# FPGA_CONFIG.net
KiCad netlist of a schematic drawn in Altium Designer
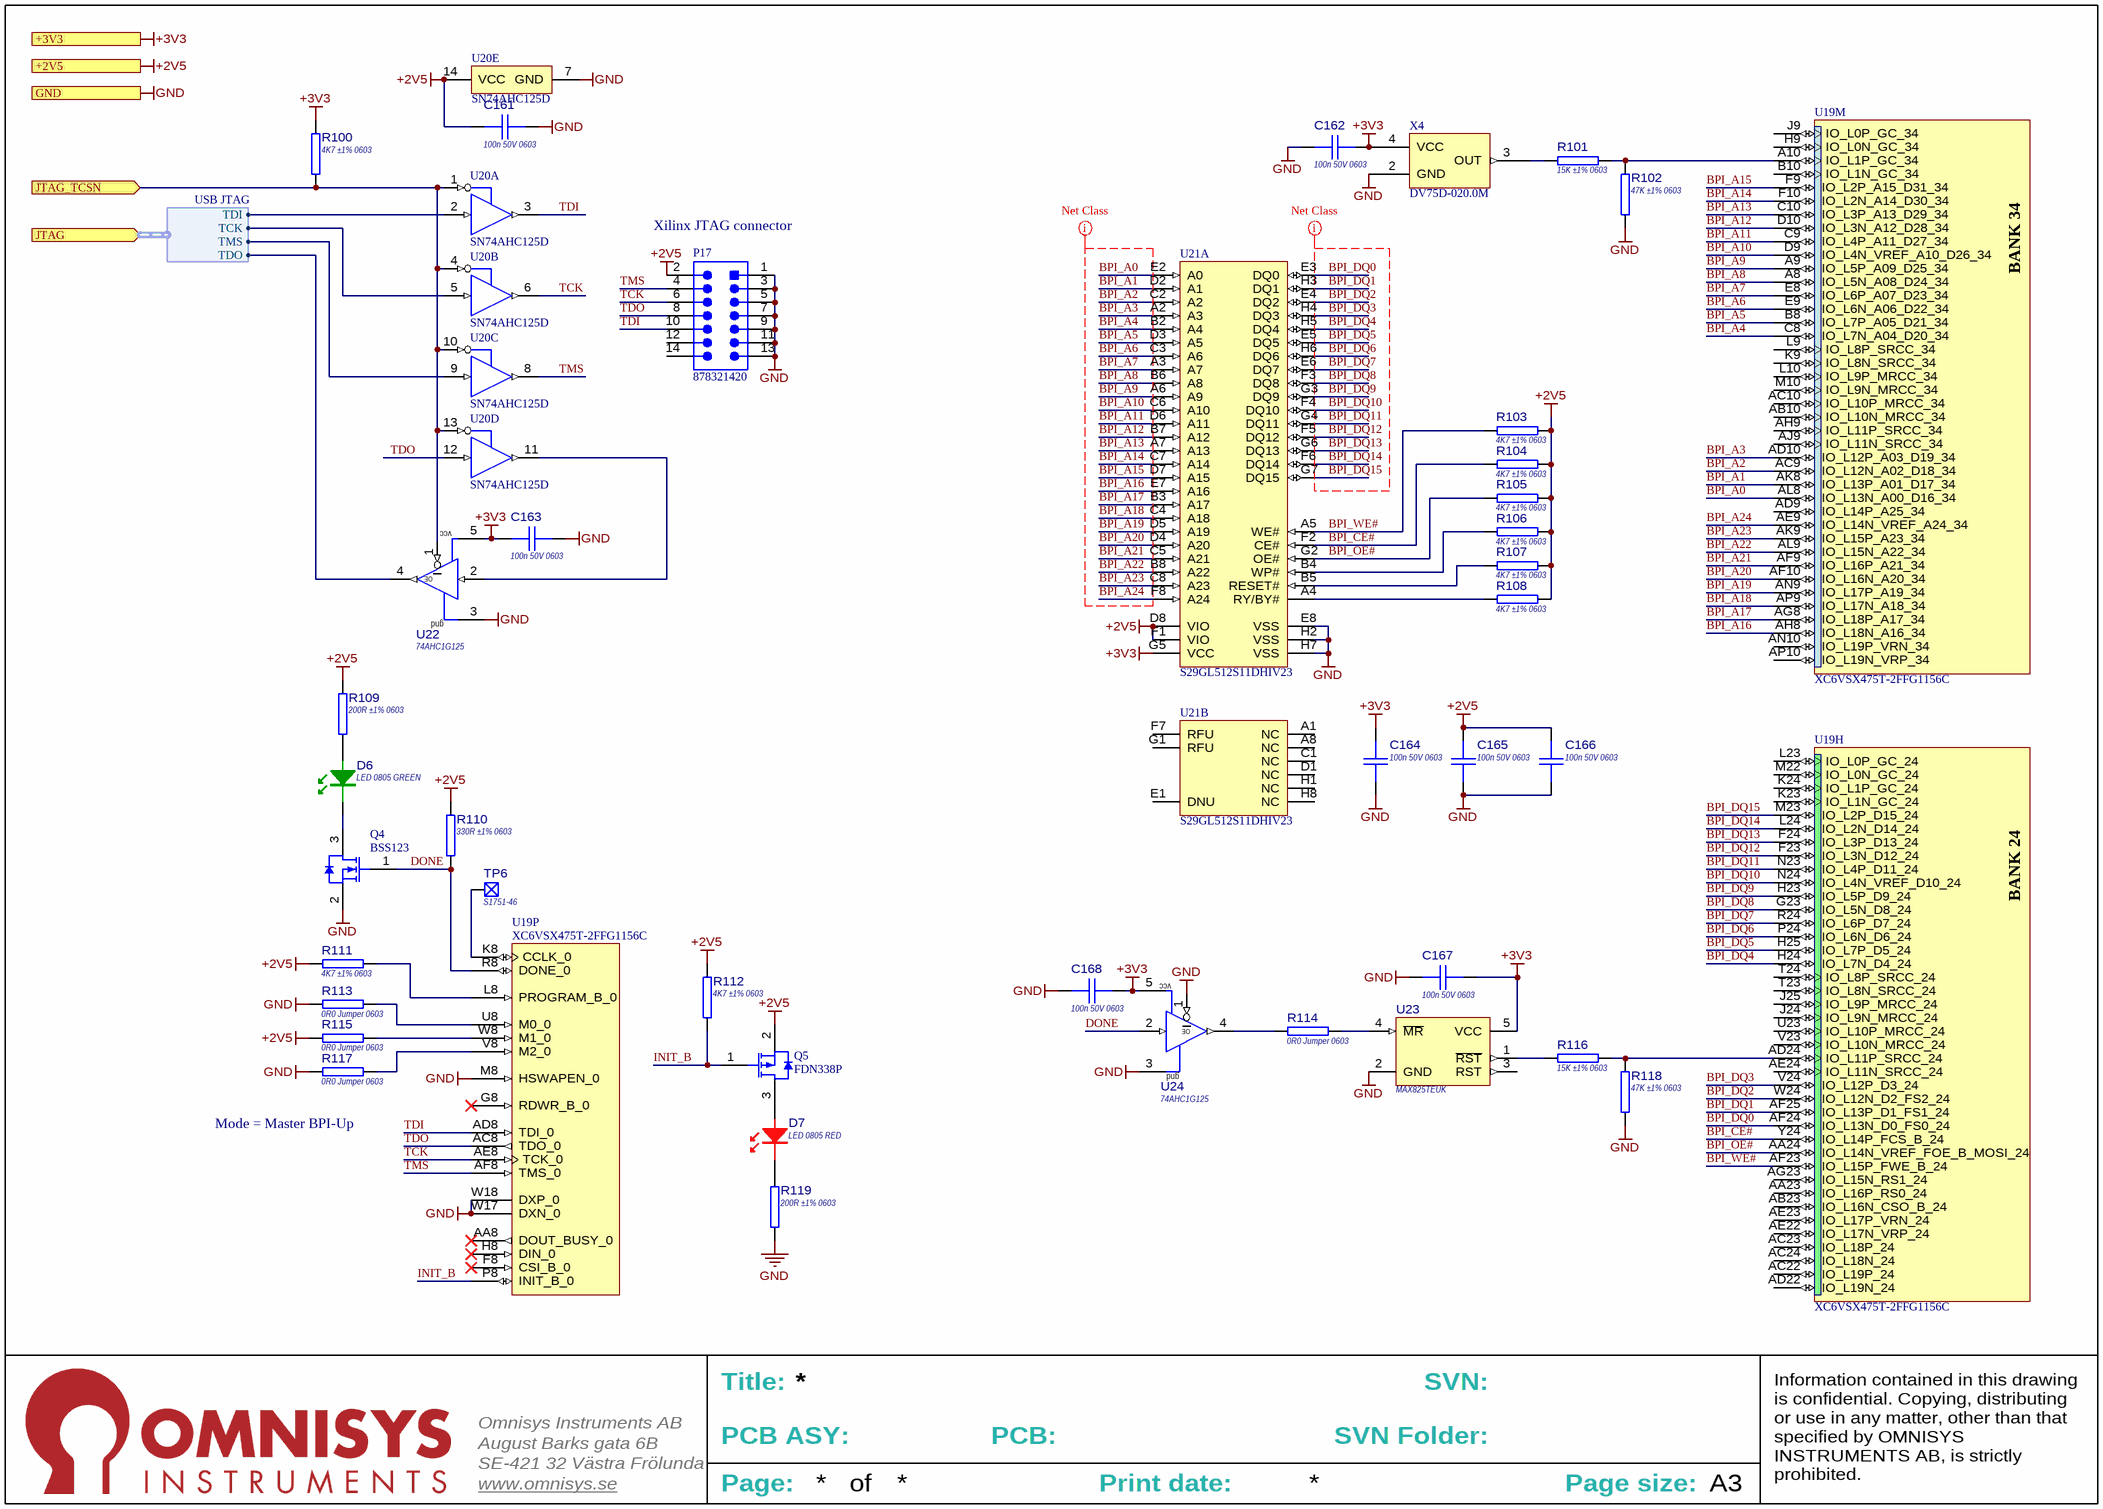
[diagram p0: FPGA_CONFIG.SchDoc]

(export (version "E")
  (design (tool "Eeschema 10.0.6"))
  (components
    (comp (ref "C161")
      (value "100n 50V 0603")
      (footprint "CAPC1608X90N")
      (description "100n 50V X7R ±10% 0603 (1608 metric)")
      (fields (field (name "PARTNUMBER") "GRM188R71H104KA93") (field (name "TOLERANCE") "±10%"))
      (libsource (lib "Omnisys Vault") (part "CAP-2PIN"))
    )
    (comp (ref "C162")
      (value "100n 50V 0603")
      (footprint "CAPC1608X90N")
      (description "100n 50V X7R ±10% 0603 (1608 metric)")
      (fields (field (name "PARTNUMBER") "GRM188R71H104KA93") (field (name "TOLERANCE") "±10%"))
      (libsource (lib "Omnisys Vault") (part "CAP-2PIN"))
    )
    (comp (ref "C163")
      (value "100n 50V 0603")
      (footprint "CAPC1608X90N")
      (description "100n 50V X7R ±10% 0603 (1608 metric)")
      (fields (field (name "PARTNUMBER") "GRM188R71H104KA93") (field (name "TOLERANCE") "±10%"))
      (libsource (lib "Omnisys Vault") (part "CAP-2PIN"))
    )
    (comp (ref "C164")
      (value "100n 50V 0603")
      (footprint "CAPC1608X90N")
      (description "100n 50V X7R ±10% 0603 (1608 metric)")
      (fields (field (name "PARTNUMBER") "GRM188R71H104KA93") (field (name "TOLERANCE") "±10%"))
      (libsource (lib "Omnisys Vault") (part "CAP-2PIN"))
    )
    (comp (ref "C165")
      (value "100n 50V 0603")
      (footprint "CAPC1608X90N")
      (description "100n 50V X7R ±10% 0603 (1608 metric)")
      (fields (field (name "PARTNUMBER") "GRM188R71H104KA93") (field (name "TOLERANCE") "±10%"))
      (libsource (lib "Omnisys Vault") (part "CAP-2PIN"))
    )
    (comp (ref "C166")
      (value "100n 50V 0603")
      (footprint "CAPC1608X90N")
      (description "100n 50V X7R ±10% 0603 (1608 metric)")
      (fields (field (name "PARTNUMBER") "GRM188R71H104KA93") (field (name "TOLERANCE") "±10%"))
      (libsource (lib "Omnisys Vault") (part "CAP-2PIN"))
    )
    (comp (ref "C167")
      (value "100n 50V 0603")
      (footprint "CAPC1608X90N")
      (description "100n 50V X7R ±10% 0603 (1608 metric)")
      (fields (field (name "PARTNUMBER") "GRM188R71H104KA93") (field (name "TOLERANCE") "±10%"))
      (libsource (lib "Omnisys Vault") (part "CAP-2PIN"))
    )
    (comp (ref "C168")
      (value "100n 50V 0603")
      (footprint "CAPC1608X90N")
      (description "100n 50V X7R ±10% 0603 (1608 metric)")
      (fields (field (name "PARTNUMBER") "GRM188R71H104KA93") (field (name "TOLERANCE") "±10%"))
      (libsource (lib "Omnisys Vault") (part "CAP-2PIN"))
    )
    (comp (ref "D6")
      (value "LED 0805 GREEN")
      (footprint "LED2012-GREEN")
      (libsource (lib "Omnisys Vault") (part "LED-2PIN-GREEN"))
    )
    (comp (ref "D7")
      (value "LED 0805 RED")
      (footprint "LED2012-RED")
      (libsource (lib "Omnisys Vault") (part "LED-2PIN-RED"))
    )
    (comp (ref "P17")
      (value "878321420")
      (footprint "MOLX-878321420_V")
      (description "Male Header, Pitch 2 mm, 2 x 7 Position, Height 7.6 mm, -55 to 105 degC, RoHS")
      (fields (field (name "MANUFACTURER") "Molex"))
      (libsource (lib "Altium Content Vault") (part "CN-2P-M-R14"))
    )
    (comp (ref "Q4")
      (value "BSS123")
      (footprint "FAIR-SOT23-3_V")
      (fields (field (name "MANUFACTURER") "Fairchild"))
      (libsource (lib "Altium Content Vault") (part "NEMOS-GSD-3"))
    )
    (comp (ref "Q5")
      (value "FDN338P")
      (footprint "FAIR-SSOT3L-3_V")
      (fields (field (name "MANUFACTURER") "Fairchild Semiconductor"))
      (libsource (lib "Altium Content Vault") (part "PEMOS-GSD-3"))
    )
    (comp (ref "R100")
      (value "4K7 ±1% 0603")
      (footprint "RESC1608N")
      (description "4K7 ±1% ±100 ppm/˚C 0.10W 75V 0603 (1608 metric)")
      (fields (field (name "POWER") "100mW") (field (name "TOLERANCE") "1%"))
      (libsource (lib "Omnisys Vault") (part "RES-2PIN"))
    )
    (comp (ref "R101")
      (value "15K ±1% 0603")
      (footprint "RESC1608N")
      (description "15K ±1% ±100 ppm/˚C 0.10W 75V 0603 (1608 metric)")
      (fields (field (name "POWER") "100mW") (field (name "TOLERANCE") "1%"))
      (libsource (lib "Omnisys Vault") (part "RES-2PIN"))
    )
    (comp (ref "R102")
      (value "47K ±1% 0603")
      (footprint "RESC1608N")
      (description "47K ±1% ±100 ppm/˚C 0.10W 75V 0603 (1608 metric)")
      (fields (field (name "POWER") "100mW") (field (name "TOLERANCE") "1%"))
      (libsource (lib "Omnisys Vault") (part "RES-2PIN"))
    )
    (comp (ref "R103")
      (value "4K7 ±1% 0603")
      (footprint "RESC1608N")
      (description "4K7 ±1% ±100 ppm/˚C 0.10W 75V 0603 (1608 metric)")
      (fields (field (name "POWER") "100mW") (field (name "TOLERANCE") "1%"))
      (libsource (lib "Omnisys Vault") (part "RES-2PIN"))
    )
    (comp (ref "R104")
      (value "4K7 ±1% 0603")
      (footprint "RESC1608N")
      (description "4K7 ±1% ±100 ppm/˚C 0.10W 75V 0603 (1608 metric)")
      (fields (field (name "POWER") "100mW") (field (name "TOLERANCE") "1%"))
      (libsource (lib "Omnisys Vault") (part "RES-2PIN"))
    )
    (comp (ref "R105")
      (value "4K7 ±1% 0603")
      (footprint "RESC1608N")
      (description "4K7 ±1% ±100 ppm/˚C 0.10W 75V 0603 (1608 metric)")
      (fields (field (name "POWER") "100mW") (field (name "TOLERANCE") "1%"))
      (libsource (lib "Omnisys Vault") (part "RES-2PIN"))
    )
    (comp (ref "R106")
      (value "4K7 ±1% 0603")
      (footprint "RESC1608N")
      (description "4K7 ±1% ±100 ppm/˚C 0.10W 75V 0603 (1608 metric)")
      (fields (field (name "POWER") "100mW") (field (name "TOLERANCE") "1%"))
      (libsource (lib "Omnisys Vault") (part "RES-2PIN"))
    )
    (comp (ref "R107")
      (value "4K7 ±1% 0603")
      (footprint "RESC1608N")
      (description "4K7 ±1% ±100 ppm/˚C 0.10W 75V 0603 (1608 metric)")
      (fields (field (name "POWER") "100mW") (field (name "TOLERANCE") "1%"))
      (libsource (lib "Omnisys Vault") (part "RES-2PIN"))
    )
    (comp (ref "R108")
      (value "4K7 ±1% 0603")
      (footprint "RESC1608N")
      (description "4K7 ±1% ±100 ppm/˚C 0.10W 75V 0603 (1608 metric)")
      (fields (field (name "POWER") "100mW") (field (name "TOLERANCE") "1%"))
      (libsource (lib "Omnisys Vault") (part "RES-2PIN"))
    )
    (comp (ref "R109")
      (value "200R ±1% 0603")
      (footprint "RESC1608N")
      (description "200R ±1% ±100 ppm/˚C 0.10W 75V 0603 (1608 metric)")
      (fields (field (name "POWER") "100mW") (field (name "TOLERANCE") "1%"))
      (libsource (lib "Omnisys Vault") (part "RES-2PIN"))
    )
    (comp (ref "R110")
      (value "330R ±1% 0603")
      (footprint "RESC1608N")
      (description "330R ±1% ±100 ppm/˚C 0.10W 75V 0603 (1608 metric)")
      (fields (field (name "POWER") "100mW") (field (name "TOLERANCE") "1%"))
      (libsource (lib "Omnisys Vault") (part "RES-2PIN"))
    )
    (comp (ref "R111")
      (value "4K7 ±1% 0603")
      (footprint "RESC1608N")
      (description "4K7 ±1% ±100 ppm/˚C 0.10W 75V 0603 (1608 metric)")
      (fields (field (name "POWER") "100mW") (field (name "TOLERANCE") "1%"))
      (libsource (lib "Omnisys Vault") (part "RES-2PIN"))
    )
    (comp (ref "R112")
      (value "4K7 ±1% 0603")
      (footprint "RESC1608N")
      (description "4K7 ±1% ±100 ppm/˚C 0.10W 75V 0603 (1608 metric)")
      (fields (field (name "POWER") "100mW") (field (name "TOLERANCE") "1%"))
      (libsource (lib "Omnisys Vault") (part "RES-2PIN"))
    )
    (comp (ref "R113")
      (value "0R0 Jumper 0603")
      (footprint "RESC1608N")
      (description "0R0 Jumper 75V 0603 (1608 metric) Max 2.0A")
      (fields (field (name "TOLERANCE") "0%") (field (name "POWER") "0W"))
      (libsource (lib "Omnisys Vault") (part "RES-2PIN"))
    )
    (comp (ref "R114")
      (value "0R0 Jumper 0603")
      (footprint "RESC1608N")
      (description "0R0 Jumper 75V 0603 (1608 metric) Max 2.0A")
      (fields (field (name "TOLERANCE") "0%") (field (name "POWER") "0W"))
      (libsource (lib "Omnisys Vault") (part "RES-2PIN"))
    )
    (comp (ref "R115")
      (value "0R0 Jumper 0603")
      (footprint "RESC1608N")
      (description "0R0 Jumper 75V 0603 (1608 metric) Max 2.0A")
      (fields (field (name "TOLERANCE") "0%") (field (name "POWER") "0W"))
      (libsource (lib "Omnisys Vault") (part "RES-2PIN"))
    )
    (comp (ref "R116")
      (value "15K ±1% 0603")
      (footprint "RESC1608N")
      (description "15K ±1% ±100 ppm/˚C 0.10W 75V 0603 (1608 metric)")
      (fields (field (name "POWER") "100mW") (field (name "TOLERANCE") "1%"))
      (libsource (lib "Omnisys Vault") (part "RES-2PIN"))
    )
    (comp (ref "R117")
      (value "0R0 Jumper 0603")
      (footprint "RESC1608N")
      (description "0R0 Jumper 75V 0603 (1608 metric) Max 2.0A")
      (fields (field (name "TOLERANCE") "0%") (field (name "POWER") "0W"))
      (libsource (lib "Omnisys Vault") (part "RES-2PIN"))
    )
    (comp (ref "R118")
      (value "47K ±1% 0603")
      (footprint "RESC1608N")
      (description "47K ±1% ±100 ppm/˚C 0.10W 75V 0603 (1608 metric)")
      (fields (field (name "POWER") "100mW") (field (name "TOLERANCE") "1%"))
      (libsource (lib "Omnisys Vault") (part "RES-2PIN"))
    )
    (comp (ref "R119")
      (value "200R ±1% 0603")
      (footprint "RESC1608N")
      (description "200R ±1% ±100 ppm/˚C 0.10W 75V 0603 (1608 metric)")
      (fields (field (name "POWER") "100mW") (field (name "TOLERANCE") "1%"))
      (libsource (lib "Omnisys Vault") (part "RES-2PIN"))
    )
    (comp (ref "TP6")
      (value "S1751-46")
      (footprint "S1751-46")
      (description "SMD Test point clip")
      (libsource (lib "Omnisys Vault") (part "1-PIN_TP"))
    )
    (comp (ref "U19")
      (value "XC6VSX475T-2FFG1156C")
      (footprint "FFG1156")
      (libsource (lib "Altium Content Vault") (part "FPGA-XVR6-XC6VXXXXXT-GA1156"))
    )
    (comp (ref "U20")
      (value "SN74AHC125D")
      (footprint "SOIC127P600X175-14N")
      (description "Buffer/Line Driver 4-CH Non-Inverting 3-ST CMOS 14-Pin SOIC Tube")
      (libsource (lib "Omnisys Vault") (part "SN74AHC125D"))
    )
    (comp (ref "U21")
      (value "S29GL512S11DHIV23")
      (footprint "BGA64C100P8X8_900X900X140")
      (description "IC FLASH MEM 512MBIT PAGE 64BGA")
      (libsource (lib "Omnisys Vault") (part "S29GL512S11DHIV23"))
    )
    (comp (ref "U22")
      (value "74AHC1G125")
      (footprint "SOT95P280X100-5N")
      (description "Single bus buffer gate with 3-state output")
      (libsource (lib "Omnisys Vault") (part "74AHC1G125"))
    )
    (comp (ref "U23")
      (value "MAX825TEUK")
      (footprint "SOT95P280X100-5N")
      (description "Microprocessor Supervisory Circuits With Watchdog Timer and Manual Reset SOT-23-5, reset th: 3.08V")
      (libsource (lib "Omnisys Vault") (part "MAX825_EUK"))
    )
    (comp (ref "U24")
      (value "74AHC1G125")
      (footprint "SOT95P280X100-5N")
      (description "Single bus buffer gate with 3-state output")
      (libsource (lib "Omnisys Vault") (part "74AHC1G125"))
    )
    (comp (ref "X4")
      (value "DV75D-020.0M")
      (footprint "SON127P420X200-4N")
      (description "OSC TCXO 20.000MHZ LVCMOS SMD")
      (libsource (lib "Omnisys Vault") (part "DV75D-020.0M"))
    )
  )
  (nets
    (net (code "3") (name "+2V5") (class "Default")
      (node (ref "C161") (pin "1") (pinfunction "1_1") (pintype "passive"))
      (node (ref "C165") (pin "1") (pinfunction "1_1") (pintype "passive"))
      (node (ref "C166") (pin "1") (pinfunction "1_1") (pintype "passive"))
      (node (ref "P17") (pin "2") (pinfunction "2_2") (pintype "passive"))
      (node (ref "Q5") (pin "2") (pinfunction "SOURCE_2") (pintype "passive"))
      (node (ref "R103") (pin "1") (pinfunction "1_1") (pintype "passive"))
      (node (ref "R104") (pin "1") (pinfunction "1_1") (pintype "passive"))
      (node (ref "R105") (pin "1") (pinfunction "1_1") (pintype "passive"))
      (node (ref "R106") (pin "1") (pinfunction "1_1") (pintype "passive"))
      (node (ref "R107") (pin "1") (pinfunction "1_1") (pintype "passive"))
      (node (ref "R108") (pin "1") (pinfunction "1_1") (pintype "passive"))
      (node (ref "R109") (pin "2") (pinfunction "2_2") (pintype "passive"))
      (node (ref "R110") (pin "1") (pinfunction "1_1") (pintype "passive"))
      (node (ref "R111") (pin "2") (pinfunction "2_2") (pintype "passive"))
      (node (ref "R112") (pin "1") (pinfunction "1_1") (pintype "passive"))
      (node (ref "R115") (pin "1") (pinfunction "1_1") (pintype "passive"))
      (node (ref "U20") (pin "14") (pinfunction "VCC_14") (pintype "power_in"))
      (node (ref "U21") (pin "D8") (pinfunction "VIO_D8") (pintype "power_in"))
      (node (ref "U21") (pin "F1") (pinfunction "VIO_F1") (pintype "power_in"))
    )
    (net (code "4") (name "+3V3") (class "Default")
      (node (ref "C162") (pin "1") (pinfunction "1_1") (pintype "passive"))
      (node (ref "C163") (pin "1") (pinfunction "1_1") (pintype "passive"))
      (node (ref "C164") (pin "1") (pinfunction "1_1") (pintype "passive"))
      (node (ref "C167") (pin "2") (pinfunction "2_2") (pintype "passive"))
      (node (ref "C168") (pin "1") (pinfunction "1_1") (pintype "passive"))
      (node (ref "R100") (pin "2") (pinfunction "2_2") (pintype "passive"))
      (node (ref "U21") (pin "G5") (pinfunction "VCC_G5") (pintype "power_in"))
      (node (ref "U22") (pin "5") (pinfunction "VCC_5") (pintype "power_in"))
      (node (ref "U23") (pin "5") (pinfunction "VCC_5") (pintype "power_in"))
      (node (ref "U24") (pin "5") (pinfunction "VCC_5") (pintype "power_in"))
      (node (ref "X4") (pin "4") (pinfunction "VCC_4") (pintype "power_in"))
    )
    (net (code "5") (name "/BPI_A0") (class "Default")
      (node (ref "U19") (pin "AL8") (pinfunction "IO_L13N_A00_D16_34_AL8") (pintype "bidirectional"))
      (node (ref "U21") (pin "E2") (pinfunction "A0_E2") (pintype "input"))
    )
    (net (code "6") (name "/BPI_A1") (class "Default")
      (node (ref "U19") (pin "AK8") (pinfunction "IO_L13P_A01_D17_34_AK8") (pintype "bidirectional"))
      (node (ref "U21") (pin "D2") (pinfunction "A1_D2") (pintype "input"))
    )
    (net (code "7") (name "/BPI_A2") (class "Default")
      (node (ref "U19") (pin "AC9") (pinfunction "IO_L12N_A02_D18_34_AC9") (pintype "bidirectional"))
      (node (ref "U21") (pin "C2") (pinfunction "A2_C2") (pintype "input"))
    )
    (net (code "8") (name "/BPI_A3") (class "Default")
      (node (ref "U19") (pin "AD10") (pinfunction "IO_L12P_A03_D19_34_AD10") (pintype "bidirectional"))
      (node (ref "U21") (pin "A2") (pinfunction "A3_A2") (pintype "input"))
    )
    (net (code "9") (name "/BPI_A4") (class "Default")
      (node (ref "U19") (pin "C8") (pinfunction "IO_L7N_A04_D20_34_C8") (pintype "bidirectional"))
      (node (ref "U21") (pin "B2") (pinfunction "A4_B2") (pintype "input"))
    )
    (net (code "10") (name "/BPI_A5") (class "Default")
      (node (ref "U19") (pin "B8") (pinfunction "IO_L7P_A05_D21_34_B8") (pintype "bidirectional"))
      (node (ref "U21") (pin "D3") (pinfunction "A5_D3") (pintype "input"))
    )
    (net (code "11") (name "/BPI_A6") (class "Default")
      (node (ref "U19") (pin "E9") (pinfunction "IO_L6N_A06_D22_34_E9") (pintype "bidirectional"))
      (node (ref "U21") (pin "C3") (pinfunction "A6_C3") (pintype "input"))
    )
    (net (code "12") (name "/BPI_A7") (class "Default")
      (node (ref "U19") (pin "E8") (pinfunction "IO_L6P_A07_D23_34_E8") (pintype "bidirectional"))
      (node (ref "U21") (pin "A3") (pinfunction "A7_A3") (pintype "input"))
    )
    (net (code "13") (name "/BPI_A8") (class "Default")
      (node (ref "U19") (pin "A8") (pinfunction "IO_L5N_A08_D24_34_A8") (pintype "bidirectional"))
      (node (ref "U21") (pin "B6") (pinfunction "A8_B6") (pintype "input"))
    )
    (net (code "14") (name "/BPI_A9") (class "Default")
      (node (ref "U19") (pin "A9") (pinfunction "IO_L5P_A09_D25_34_A9") (pintype "bidirectional"))
      (node (ref "U21") (pin "A6") (pinfunction "A9_A6") (pintype "input"))
    )
    (net (code "15") (name "/BPI_A10") (class "Default")
      (node (ref "U19") (pin "D9") (pinfunction "IO_L4N_VREF_A10_D26_34_D9") (pintype "bidirectional"))
      (node (ref "U21") (pin "C6") (pinfunction "A10_C6") (pintype "input"))
    )
    (net (code "16") (name "/BPI_A11") (class "Default")
      (node (ref "U19") (pin "C9") (pinfunction "IO_L4P_A11_D27_34_C9") (pintype "bidirectional"))
      (node (ref "U21") (pin "D6") (pinfunction "A11_D6") (pintype "input"))
    )
    (net (code "17") (name "/BPI_A12") (class "Default")
      (node (ref "U19") (pin "D10") (pinfunction "IO_L3N_A12_D28_34_D10") (pintype "bidirectional"))
      (node (ref "U21") (pin "B7") (pinfunction "A12_B7") (pintype "input"))
    )
    (net (code "18") (name "/BPI_A13") (class "Default")
      (node (ref "U19") (pin "C10") (pinfunction "IO_L3P_A13_D29_34_C10") (pintype "bidirectional"))
      (node (ref "U21") (pin "A7") (pinfunction "A13_A7") (pintype "input"))
    )
    (net (code "19") (name "/BPI_A14") (class "Default")
      (node (ref "U19") (pin "F10") (pinfunction "IO_L2N_A14_D30_34_F10") (pintype "bidirectional"))
      (node (ref "U21") (pin "C7") (pinfunction "A14_C7") (pintype "input"))
    )
    (net (code "20") (name "/BPI_A15") (class "Default")
      (node (ref "U19") (pin "F9") (pinfunction "IO_L2P_A15_D31_34_F9") (pintype "bidirectional"))
      (node (ref "U21") (pin "D7") (pinfunction "A15_D7") (pintype "input"))
    )
    (net (code "21") (name "/BPI_A16") (class "Default")
      (node (ref "U19") (pin "AH8") (pinfunction "IO_L18N_A16_34_AH8") (pintype "bidirectional"))
      (node (ref "U21") (pin "E7") (pinfunction "A16_E7") (pintype "input"))
    )
    (net (code "22") (name "/BPI_A17") (class "Default")
      (node (ref "U19") (pin "AG8") (pinfunction "IO_L18P_A17_34_AG8") (pintype "bidirectional"))
      (node (ref "U21") (pin "B3") (pinfunction "A17_B3") (pintype "input"))
    )
    (net (code "23") (name "/BPI_A18") (class "Default")
      (node (ref "U19") (pin "AP9") (pinfunction "IO_L17N_A18_34_AP9") (pintype "bidirectional"))
      (node (ref "U21") (pin "C4") (pinfunction "A18_C4") (pintype "input"))
    )
    (net (code "24") (name "/BPI_A19") (class "Default")
      (node (ref "U19") (pin "AN9") (pinfunction "IO_L17P_A19_34_AN9") (pintype "bidirectional"))
      (node (ref "U21") (pin "D5") (pinfunction "A19_D5") (pintype "input"))
    )
    (net (code "25") (name "/BPI_A20") (class "Default")
      (node (ref "U19") (pin "AF10") (pinfunction "IO_L16N_A20_34_AF10") (pintype "bidirectional"))
      (node (ref "U21") (pin "D4") (pinfunction "A20_D4") (pintype "input"))
    )
    (net (code "26") (name "/BPI_A21") (class "Default")
      (node (ref "U19") (pin "AF9") (pinfunction "IO_L16P_A21_34_AF9") (pintype "bidirectional"))
      (node (ref "U21") (pin "C5") (pinfunction "A21_C5") (pintype "input"))
    )
    (net (code "27") (name "/BPI_A22") (class "Default")
      (node (ref "U19") (pin "AL9") (pinfunction "IO_L15N_A22_34_AL9") (pintype "bidirectional"))
      (node (ref "U21") (pin "B8") (pinfunction "A22_B8") (pintype "input"))
    )
    (net (code "28") (name "/BPI_A23") (class "Default")
      (node (ref "U19") (pin "AK9") (pinfunction "IO_L15P_A23_34_AK9") (pintype "bidirectional"))
      (node (ref "U21") (pin "C8") (pinfunction "A23_C8") (pintype "input"))
    )
    (net (code "29") (name "/BPI_A24") (class "Default")
      (node (ref "U19") (pin "AE9") (pinfunction "IO_L14N_VREF_A24_34_AE9") (pintype "bidirectional"))
      (node (ref "U21") (pin "F8") (pinfunction "A24_F8") (pintype "input"))
    )
    (net (code "30") (name "/BPI_CE#") (class "Default")
      (node (ref "R104") (pin "2") (pinfunction "2_2") (pintype "passive"))
      (node (ref "U19") (pin "Y24") (pinfunction "IO_L14P_FCS_B_24_Y24") (pintype "bidirectional"))
      (node (ref "U21") (pin "F2") (pinfunction "CE#_F2") (pintype "input"))
    )
    (net (code "31") (name "/BPI_DQ0") (class "Default")
      (node (ref "U19") (pin "AF24") (pinfunction "IO_L13N_D0_FS0_24_AF24") (pintype "bidirectional"))
      (node (ref "U21") (pin "E3") (pinfunction "DQ0_E3") (pintype "bidirectional"))
    )
    (net (code "32") (name "/BPI_DQ1") (class "Default")
      (node (ref "U19") (pin "AF25") (pinfunction "IO_L13P_D1_FS1_24_AF25") (pintype "bidirectional"))
      (node (ref "U21") (pin "H3") (pinfunction "DQ1_H3") (pintype "bidirectional"))
    )
    (net (code "33") (name "/BPI_DQ2") (class "Default")
      (node (ref "U19") (pin "W24") (pinfunction "IO_L12N_D2_FS2_24_W24") (pintype "bidirectional"))
      (node (ref "U21") (pin "E4") (pinfunction "DQ2_E4") (pintype "bidirectional"))
    )
    (net (code "34") (name "/BPI_DQ3") (class "Default")
      (node (ref "U19") (pin "V24") (pinfunction "IO_L12P_D3_24_V24") (pintype "bidirectional"))
      (node (ref "U21") (pin "H4") (pinfunction "DQ3_H4") (pintype "bidirectional"))
    )
    (net (code "35") (name "/BPI_DQ4") (class "Default")
      (node (ref "U19") (pin "H24") (pinfunction "IO_L7N_D4_24_H24") (pintype "bidirectional"))
      (node (ref "U21") (pin "H5") (pinfunction "DQ4_H5") (pintype "bidirectional"))
    )
    (net (code "36") (name "/BPI_DQ5") (class "Default")
      (node (ref "U19") (pin "H25") (pinfunction "IO_L7P_D5_24_H25") (pintype "bidirectional"))
      (node (ref "U21") (pin "E5") (pinfunction "DQ5_E5") (pintype "bidirectional"))
    )
    (net (code "37") (name "/BPI_DQ6") (class "Default")
      (node (ref "U19") (pin "P24") (pinfunction "IO_L6N_D6_24_P24") (pintype "bidirectional"))
      (node (ref "U21") (pin "H6") (pinfunction "DQ6_H6") (pintype "bidirectional"))
    )
    (net (code "38") (name "/BPI_DQ7") (class "Default")
      (node (ref "U19") (pin "R24") (pinfunction "IO_L6P_D7_24_R24") (pintype "bidirectional"))
      (node (ref "U21") (pin "E6") (pinfunction "DQ7_E6") (pintype "bidirectional"))
    )
    (net (code "39") (name "/BPI_DQ8") (class "Default")
      (node (ref "U19") (pin "G23") (pinfunction "IO_L5N_D8_24_G23") (pintype "bidirectional"))
      (node (ref "U21") (pin "F3") (pinfunction "DQ8_F3") (pintype "bidirectional"))
    )
    (net (code "40") (name "/BPI_DQ9") (class "Default")
      (node (ref "U19") (pin "H23") (pinfunction "IO_L5P_D9_24_H23") (pintype "bidirectional"))
      (node (ref "U21") (pin "G3") (pinfunction "DQ9_G3") (pintype "bidirectional"))
    )
    (net (code "41") (name "/BPI_DQ10") (class "Default")
      (node (ref "U19") (pin "N24") (pinfunction "IO_L4N_VREF_D10_24_N24") (pintype "bidirectional"))
      (node (ref "U21") (pin "F4") (pinfunction "DQ10_F4") (pintype "bidirectional"))
    )
    (net (code "42") (name "/BPI_DQ11") (class "Default")
      (node (ref "U19") (pin "N23") (pinfunction "IO_L4P_D11_24_N23") (pintype "bidirectional"))
      (node (ref "U21") (pin "G4") (pinfunction "DQ11_G4") (pintype "bidirectional"))
    )
    (net (code "43") (name "/BPI_DQ12") (class "Default")
      (node (ref "U19") (pin "F23") (pinfunction "IO_L3N_D12_24_F23") (pintype "bidirectional"))
      (node (ref "U21") (pin "F5") (pinfunction "DQ12_F5") (pintype "bidirectional"))
    )
    (net (code "44") (name "/BPI_DQ13") (class "Default")
      (node (ref "U19") (pin "F24") (pinfunction "IO_L3P_D13_24_F24") (pintype "bidirectional"))
      (node (ref "U21") (pin "G6") (pinfunction "DQ13_G6") (pintype "bidirectional"))
    )
    (net (code "45") (name "/BPI_DQ14") (class "Default")
      (node (ref "U19") (pin "L24") (pinfunction "IO_L2N_D14_24_L24") (pintype "bidirectional"))
      (node (ref "U21") (pin "F6") (pinfunction "DQ14_F6") (pintype "bidirectional"))
    )
    (net (code "46") (name "/BPI_DQ15") (class "Default")
      (node (ref "U19") (pin "M23") (pinfunction "IO_L2P_D15_24_M23") (pintype "bidirectional"))
      (node (ref "U21") (pin "G7") (pinfunction "DQ15_G7") (pintype "bidirectional"))
    )
    (net (code "47") (name "/BPI_OE#") (class "Default")
      (node (ref "R105") (pin "2") (pinfunction "2_2") (pintype "passive"))
      (node (ref "U19") (pin "AA24") (pinfunction "IO_L14N_VREF_FOE_B_MOSI_24_AA24") (pintype "bidirectional"))
      (node (ref "U21") (pin "G2") (pinfunction "OE#_G2") (pintype "input"))
    )
    (net (code "48") (name "/BPI_WE#") (class "Default")
      (node (ref "R103") (pin "2") (pinfunction "2_2") (pintype "passive"))
      (node (ref "U19") (pin "AF23") (pinfunction "IO_L15P_FWE_B_24_AF23") (pintype "bidirectional"))
      (node (ref "U21") (pin "A5") (pinfunction "WE#_A5") (pintype "input"))
    )
    (net (code "49") (name "/DONE") (class "Default")
      (node (ref "Q4") (pin "1") (pinfunction "G_1") (pintype "passive"))
      (node (ref "R110") (pin "2") (pinfunction "2_2") (pintype "passive"))
      (node (ref "U19") (pin "R8") (pinfunction "DONE_0_R8") (pintype "bidirectional"))
      (node (ref "U24") (pin "2") (pinfunction "B_2") (pintype "input"))
    )
    (net (code "50") (name "/INIT_B") (class "Default")
      (node (ref "Q5") (pin "1") (pinfunction "GATE_1") (pintype "passive"))
      (node (ref "R112") (pin "2") (pinfunction "2_2") (pintype "passive"))
      (node (ref "U19") (pin "P8") (pinfunction "INIT_B_0_P8") (pintype "bidirectional"))
    )
    (net (code "51") (name "/JTAG_TCSN") (class "Default")
      (node (ref "R100") (pin "1") (pinfunction "1_1") (pintype "passive"))
      (node (ref "U20") (pin "1") (pinfunction "1OE#_1") (pintype "input"))
      (node (ref "U20") (pin "10") (pinfunction "3OE#_10") (pintype "input"))
      (node (ref "U20") (pin "13") (pinfunction "4OE#_13") (pintype "input"))
      (node (ref "U20") (pin "4") (pinfunction "2OE#_4") (pintype "input"))
      (node (ref "U22") (pin "1") (pinfunction "~{O}E_1") (pintype "input"))
    )
    (net (code "52") (name "/TCK") (class "Default")
      (node (ref "P17") (pin "6") (pinfunction "6_6") (pintype "passive"))
      (node (ref "U19") (pin "AE8") (pinfunction "TCK_0_AE8") (pintype "input"))
      (node (ref "U20") (pin "6") (pinfunction "2Y_6") (pintype "output"))
    )
    (net (code "53") (name "/TDI") (class "Default")
      (node (ref "P17") (pin "10") (pinfunction "10_10") (pintype "passive"))
      (node (ref "U19") (pin "AD8") (pinfunction "TDI_0_AD8") (pintype "input"))
      (node (ref "U20") (pin "3") (pinfunction "1Y_3") (pintype "output"))
    )
    (net (code "54") (name "/TDO") (class "Default")
      (node (ref "P17") (pin "8") (pinfunction "8_8") (pintype "passive"))
      (node (ref "U19") (pin "AC8") (pinfunction "TDO_0_AC8") (pintype "output"))
      (node (ref "U20") (pin "12") (pinfunction "4A_12") (pintype "input"))
    )
    (net (code "55") (name "/TMS") (class "Default")
      (node (ref "P17") (pin "4") (pinfunction "4_4") (pintype "passive"))
      (node (ref "U19") (pin "AF8") (pinfunction "TMS_0_AF8") (pintype "input"))
      (node (ref "U20") (pin "8") (pinfunction "3Y_8") (pintype "output"))
    )
    (net (code "57") (name "GND") (class "Default")
      (node (ref "C161") (pin "2") (pinfunction "2_2") (pintype "passive"))
      (node (ref "C162") (pin "2") (pinfunction "2_2") (pintype "passive"))
      (node (ref "C163") (pin "2") (pinfunction "2_2") (pintype "passive"))
      (node (ref "C164") (pin "2") (pinfunction "2_2") (pintype "passive"))
      (node (ref "C165") (pin "2") (pinfunction "2_2") (pintype "passive"))
      (node (ref "C166") (pin "2") (pinfunction "2_2") (pintype "passive"))
      (node (ref "C167") (pin "1") (pinfunction "1_1") (pintype "passive"))
      (node (ref "C168") (pin "2") (pinfunction "2_2") (pintype "passive"))
      (node (ref "P17") (pin "1") (pinfunction "1_1") (pintype "passive"))
      (node (ref "P17") (pin "11") (pinfunction "11_11") (pintype "passive"))
      (node (ref "P17") (pin "13") (pinfunction "13_13") (pintype "passive"))
      (node (ref "P17") (pin "3") (pinfunction "3_3") (pintype "passive"))
      (node (ref "P17") (pin "5") (pinfunction "5_5") (pintype "passive"))
      (node (ref "P17") (pin "7") (pinfunction "7_7") (pintype "passive"))
      (node (ref "P17") (pin "9") (pinfunction "9_9") (pintype "passive"))
      (node (ref "Q4") (pin "2") (pinfunction "S_2") (pintype "passive"))
      (node (ref "R102") (pin "1") (pinfunction "1_1") (pintype "passive"))
      (node (ref "R113") (pin "1") (pinfunction "1_1") (pintype "passive"))
      (node (ref "R117") (pin "1") (pinfunction "1_1") (pintype "passive"))
      (node (ref "R118") (pin "1") (pinfunction "1_1") (pintype "passive"))
      (node (ref "R119") (pin "1") (pinfunction "1_1") (pintype "passive"))
      (node (ref "U19") (pin "M8") (pinfunction "HSWAPEN_0_M8") (pintype "input"))
      (node (ref "U19") (pin "W17") (pinfunction "DXN_0_W17") (pintype "passive"))
      (node (ref "U19") (pin "W18") (pinfunction "DXP_0_W18") (pintype "passive"))
      (node (ref "U20") (pin "7") (pinfunction "GND_7") (pintype "power_in"))
      (node (ref "U21") (pin "E8") (pinfunction "VSS_E8") (pintype "power_in"))
      (node (ref "U21") (pin "H2") (pinfunction "VSS_H2") (pintype "power_in"))
      (node (ref "U21") (pin "H7") (pinfunction "VSS_H7") (pintype "power_in"))
      (node (ref "U22") (pin "3") (pinfunction "GND_3") (pintype "power_in"))
      (node (ref "U23") (pin "2") (pinfunction "GND_2") (pintype "power_in"))
      (node (ref "U24") (pin "1") (pinfunction "~{O}E_1") (pintype "input"))
      (node (ref "U24") (pin "3") (pinfunction "GND_3") (pintype "power_in"))
      (node (ref "X4") (pin "2") (pinfunction "GND_2") (pintype "power_in"))
    )
    (net (code "58") (name "Net-(D6-Pad2)") (class "Default")
      (node (ref "D6") (pin "2") (pintype "passive"))
      (node (ref "R109") (pin "1") (pinfunction "1_1") (pintype "passive"))
    )
    (net (code "59") (name "Net-(D7-Pad1)") (class "Default")
      (node (ref "D7") (pin "1") (pintype "passive"))
      (node (ref "R119") (pin "2") (pinfunction "2_2") (pintype "passive"))
    )
    (net (code "60") (name "Net-(Q4-D)") (class "Default")
      (node (ref "D6") (pin "1") (pintype "passive"))
      (node (ref "Q4") (pin "3") (pinfunction "D_3") (pintype "passive"))
    )
    (net (code "61") (name "Net-(Q5-DRAIN)") (class "Default")
      (node (ref "D7") (pin "2") (pintype "passive"))
      (node (ref "Q5") (pin "3") (pinfunction "DRAIN_3") (pintype "passive"))
    )
    (net (code "62") (name "Net-(U19H-IO_L11P_SRCC_24)") (class "Default")
      (node (ref "R116") (pin "2") (pinfunction "2_2") (pintype "passive"))
      (node (ref "R118") (pin "2") (pinfunction "2_2") (pintype "passive"))
      (node (ref "U19") (pin "AD24") (pinfunction "IO_L11P_SRCC_24_AD24") (pintype "bidirectional"))
    )
    (net (code "63") (name "Net-(U19M-IO_L1P_GC_34)") (class "Default")
      (node (ref "R101") (pin "2") (pinfunction "2_2") (pintype "passive"))
      (node (ref "R102") (pin "2") (pinfunction "2_2") (pintype "passive"))
      (node (ref "U19") (pin "A10") (pinfunction "IO_L1P_GC_34_A10") (pintype "bidirectional"))
    )
    (net (code "64") (name "Net-(U19P-CCLK_0)") (class "Default")
      (node (ref "TP6") (pin "1") (pintype "passive"))
      (node (ref "U19") (pin "K8") (pinfunction "CCLK_0_K8") (pintype "bidirectional"))
    )
    (net (code "65") (name "Net-(U19P-M0_0)") (class "Default")
      (node (ref "R113") (pin "2") (pinfunction "2_2") (pintype "passive"))
      (node (ref "U19") (pin "U8") (pinfunction "M0_0_U8") (pintype "input"))
    )
    (net (code "66") (name "Net-(U19P-M1_0)") (class "Default")
      (node (ref "R115") (pin "2") (pinfunction "2_2") (pintype "passive"))
      (node (ref "U19") (pin "W8") (pinfunction "M1_0_W8") (pintype "input"))
    )
    (net (code "67") (name "Net-(U19P-M2_0)") (class "Default")
      (node (ref "R117") (pin "2") (pinfunction "2_2") (pintype "passive"))
      (node (ref "U19") (pin "V8") (pinfunction "M2_0_V8") (pintype "input"))
    )
    (net (code "68") (name "Net-(U19P-PROGRAM_B_0)") (class "Default")
      (node (ref "R111") (pin "1") (pinfunction "1_1") (pintype "passive"))
      (node (ref "U19") (pin "L8") (pinfunction "PROGRAM_B_0_L8") (pintype "input"))
    )
    (net (code "69") (name "Net-(U20D-4Y)") (class "Default")
      (node (ref "U20") (pin "11") (pinfunction "4Y_11") (pintype "output"))
      (node (ref "U22") (pin "2") (pinfunction "B_2") (pintype "input"))
    )
    (net (code "70") (name "Net-(U21A-RESET#)") (class "Default")
      (node (ref "R107") (pin "2") (pinfunction "2_2") (pintype "passive"))
      (node (ref "U21") (pin "B5") (pinfunction "RESET#_B5") (pintype "input"))
    )
    (net (code "71") (name "Net-(U21A-RY{slash}BY#)") (class "Default")
      (node (ref "R108") (pin "2") (pinfunction "2_2") (pintype "passive"))
      (node (ref "U21") (pin "A4") (pinfunction "RY/BY#_A4") (pintype "tri_state"))
    )
    (net (code "72") (name "Net-(U21A-WP#)") (class "Default")
      (node (ref "R106") (pin "2") (pinfunction "2_2") (pintype "passive"))
      (node (ref "U21") (pin "B4") (pinfunction "WP#_B4") (pintype "input"))
    )
    (net (code "73") (name "Net-(U23-~{MR})") (class "Default")
      (node (ref "R114") (pin "1") (pinfunction "1_1") (pintype "passive"))
      (node (ref "U23") (pin "4") (pinfunction "~{MR}_4") (pintype "input"))
    )
    (net (code "74") (name "Net-(U23-~{RST})") (class "Default")
      (node (ref "R116") (pin "1") (pinfunction "1_1") (pintype "passive"))
      (node (ref "U23") (pin "1") (pinfunction "~{RST}_1") (pintype "output"))
    )
    (net (code "75") (name "Net-(U24-Y)") (class "Default")
      (node (ref "R114") (pin "2") (pinfunction "2_2") (pintype "passive"))
      (node (ref "U24") (pin "4") (pinfunction "Y_4") (pintype "output"))
    )
    (net (code "76") (name "Net-(X4-OUT)") (class "Default")
      (node (ref "R101") (pin "1") (pinfunction "1_1") (pintype "passive"))
      (node (ref "X4") (pin "3") (pinfunction "OUT_3") (pintype "output"))
    )
    (net (code "77") (name "unconnected-(P17-Pad12)") (class "Default")
      (node (ref "P17") (pin "12") (pinfunction "12_12") (pintype "passive"))
    )
    (net (code "78") (name "unconnected-(P17-Pad14)") (class "Default")
      (node (ref "P17") (pin "14") (pinfunction "14_14") (pintype "passive"))
    )
    (net (code "79") (name "unconnected-(U19H-IO_L0N_GC_24-PadM22)") (class "Default")
      (node (ref "U19") (pin "M22") (pinfunction "IO_L0N_GC_24_M22") (pintype "bidirectional"))
    )
    (net (code "80") (name "unconnected-(U19H-IO_L0P_GC_24-PadL23)") (class "Default")
      (node (ref "U19") (pin "L23") (pinfunction "IO_L0P_GC_24_L23") (pintype "bidirectional"))
    )
    (net (code "81") (name "unconnected-(U19H-IO_L1N_GC_24-PadK23)") (class "Default")
      (node (ref "U19") (pin "K23") (pinfunction "IO_L1N_GC_24_K23") (pintype "bidirectional"))
    )
    (net (code "82") (name "unconnected-(U19H-IO_L1P_GC_24-PadK24)") (class "Default")
      (node (ref "U19") (pin "K24") (pinfunction "IO_L1P_GC_24_K24") (pintype "bidirectional"))
    )
    (net (code "83") (name "unconnected-(U19H-IO_L8N_SRCC_24-PadT23)") (class "Default")
      (node (ref "U19") (pin "T23") (pinfunction "IO_L8N_SRCC_24_T23") (pintype "bidirectional"))
    )
    (net (code "84") (name "unconnected-(U19H-IO_L8P_SRCC_24-PadT24)") (class "Default")
      (node (ref "U19") (pin "T24") (pinfunction "IO_L8P_SRCC_24_T24") (pintype "bidirectional"))
    )
    (net (code "85") (name "unconnected-(U19H-IO_L9N_MRCC_24-PadJ24)") (class "Default")
      (node (ref "U19") (pin "J24") (pinfunction "IO_L9N_MRCC_24_J24") (pintype "bidirectional"))
    )
    (net (code "86") (name "unconnected-(U19H-IO_L9P_MRCC_24-PadJ25)") (class "Default")
      (node (ref "U19") (pin "J25") (pinfunction "IO_L9P_MRCC_24_J25") (pintype "bidirectional"))
    )
    (net (code "87") (name "unconnected-(U19H-IO_L10N_MRCC_24-PadV23)") (class "Default")
      (node (ref "U19") (pin "V23") (pinfunction "IO_L10N_MRCC_24_V23") (pintype "bidirectional"))
    )
    (net (code "88") (name "unconnected-(U19H-IO_L10P_MRCC_24-PadU23)") (class "Default")
      (node (ref "U19") (pin "U23") (pinfunction "IO_L10P_MRCC_24_U23") (pintype "bidirectional"))
    )
    (net (code "89") (name "unconnected-(U19H-IO_L11N_SRCC_24-PadAE24)") (class "Default")
      (node (ref "U19") (pin "AE24") (pinfunction "IO_L11N_SRCC_24_AE24") (pintype "bidirectional"))
    )
    (net (code "90") (name "unconnected-(U19H-IO_L15N_RS1_24-PadAG23)") (class "Default")
      (node (ref "U19") (pin "AG23") (pinfunction "IO_L15N_RS1_24_AG23") (pintype "bidirectional"))
    )
    (net (code "91") (name "unconnected-(U19H-IO_L16N_CSO_B_24-PadAB23)") (class "Default")
      (node (ref "U19") (pin "AB23") (pinfunction "IO_L16N_CSO_B_24_AB23") (pintype "bidirectional"))
    )
    (net (code "92") (name "unconnected-(U19H-IO_L16P_RS0_24-PadAA23)") (class "Default")
      (node (ref "U19") (pin "AA23") (pinfunction "IO_L16P_RS0_24_AA23") (pintype "bidirectional"))
    )
    (net (code "93") (name "unconnected-(U19H-IO_L17N_VRP_24-PadAE22)") (class "Default")
      (node (ref "U19") (pin "AE22") (pinfunction "IO_L17N_VRP_24_AE22") (pintype "bidirectional"))
    )
    (net (code "94") (name "unconnected-(U19H-IO_L17P_VRN_24-PadAE23)") (class "Default")
      (node (ref "U19") (pin "AE23") (pinfunction "IO_L17P_VRN_24_AE23") (pintype "bidirectional"))
    )
    (net (code "95") (name "unconnected-(U19H-IO_L18N_24-PadAC24)") (class "Default")
      (node (ref "U19") (pin "AC24") (pinfunction "IO_L18N_24_AC24") (pintype "bidirectional"))
    )
    (net (code "96") (name "unconnected-(U19H-IO_L18P_24-PadAC23)") (class "Default")
      (node (ref "U19") (pin "AC23") (pinfunction "IO_L18P_24_AC23") (pintype "bidirectional"))
    )
    (net (code "97") (name "unconnected-(U19H-IO_L19N_24-PadAD22)") (class "Default")
      (node (ref "U19") (pin "AD22") (pinfunction "IO_L19N_24_AD22") (pintype "bidirectional"))
    )
    (net (code "98") (name "unconnected-(U19H-IO_L19P_24-PadAC22)") (class "Default")
      (node (ref "U19") (pin "AC22") (pinfunction "IO_L19P_24_AC22") (pintype "bidirectional"))
    )
    (net (code "99") (name "unconnected-(U19M-IO_L0N_GC_34-PadH9)") (class "Default")
      (node (ref "U19") (pin "H9") (pinfunction "IO_L0N_GC_34_H9") (pintype "bidirectional"))
    )
    (net (code "100") (name "unconnected-(U19M-IO_L0P_GC_34-PadJ9)") (class "Default")
      (node (ref "U19") (pin "J9") (pinfunction "IO_L0P_GC_34_J9") (pintype "bidirectional"))
    )
    (net (code "101") (name "unconnected-(U19M-IO_L1N_GC_34-PadB10)") (class "Default")
      (node (ref "U19") (pin "B10") (pinfunction "IO_L1N_GC_34_B10") (pintype "bidirectional"))
    )
    (net (code "102") (name "unconnected-(U19M-IO_L8N_SRCC_34-PadK9)") (class "Default")
      (node (ref "U19") (pin "K9") (pinfunction "IO_L8N_SRCC_34_K9") (pintype "bidirectional"))
    )
    (net (code "103") (name "unconnected-(U19M-IO_L8P_SRCC_34-PadL9)") (class "Default")
      (node (ref "U19") (pin "L9") (pinfunction "IO_L8P_SRCC_34_L9") (pintype "bidirectional"))
    )
    (net (code "104") (name "unconnected-(U19M-IO_L9N_MRCC_34-PadM10)") (class "Default")
      (node (ref "U19") (pin "M10") (pinfunction "IO_L9N_MRCC_34_M10") (pintype "bidirectional"))
    )
    (net (code "105") (name "unconnected-(U19M-IO_L9P_MRCC_34-PadL10)") (class "Default")
      (node (ref "U19") (pin "L10") (pinfunction "IO_L9P_MRCC_34_L10") (pintype "bidirectional"))
    )
    (net (code "106") (name "unconnected-(U19M-IO_L10N_MRCC_34-PadAB10)") (class "Default")
      (node (ref "U19") (pin "AB10") (pinfunction "IO_L10N_MRCC_34_AB10") (pintype "bidirectional"))
    )
    (net (code "107") (name "unconnected-(U19M-IO_L10P_MRCC_34-PadAC10)") (class "Default")
      (node (ref "U19") (pin "AC10") (pinfunction "IO_L10P_MRCC_34_AC10") (pintype "bidirectional"))
    )
    (net (code "108") (name "unconnected-(U19M-IO_L11N_SRCC_34-PadAJ9)") (class "Default")
      (node (ref "U19") (pin "AJ9") (pinfunction "IO_L11N_SRCC_34_AJ9") (pintype "bidirectional"))
    )
    (net (code "109") (name "unconnected-(U19M-IO_L11P_SRCC_34-PadAH9)") (class "Default")
      (node (ref "U19") (pin "AH9") (pinfunction "IO_L11P_SRCC_34_AH9") (pintype "bidirectional"))
    )
    (net (code "110") (name "unconnected-(U19M-IO_L14P_A25_34-PadAD9)") (class "Default")
      (node (ref "U19") (pin "AD9") (pinfunction "IO_L14P_A25_34_AD9") (pintype "bidirectional"))
    )
    (net (code "111") (name "unconnected-(U19M-IO_L19N_VRP_34-PadAP10)") (class "Default")
      (node (ref "U19") (pin "AP10") (pinfunction "IO_L19N_VRP_34_AP10") (pintype "bidirectional"))
    )
    (net (code "112") (name "unconnected-(U19M-IO_L19P_VRN_34-PadAN10)") (class "Default")
      (node (ref "U19") (pin "AN10") (pinfunction "IO_L19P_VRN_34_AN10") (pintype "bidirectional"))
    )
    (net (code "113") (name "unconnected-(U19P-CSI_B_0-PadF8)") (class "Default")
      (node (ref "U19") (pin "F8") (pinfunction "CSI_B_0_F8") (pintype "input+no_connect"))
    )
    (net (code "114") (name "unconnected-(U19P-DIN_0-PadH8)") (class "Default")
      (node (ref "U19") (pin "H8") (pinfunction "DIN_0_H8") (pintype "input+no_connect"))
    )
    (net (code "115") (name "unconnected-(U19P-DOUT_BUSY_0-PadAA8)") (class "Default")
      (node (ref "U19") (pin "AA8") (pinfunction "DOUT_BUSY_0_AA8") (pintype "output+no_connect"))
    )
    (net (code "116") (name "unconnected-(U19P-RDWR_B_0-PadG8)") (class "Default")
      (node (ref "U19") (pin "G8") (pinfunction "RDWR_B_0_G8") (pintype "input+no_connect"))
    )
    (net (code "117") (name "unconnected-(U20A-1A-Pad2)") (class "Default")
      (node (ref "U20") (pin "2") (pinfunction "1A_2") (pintype "input"))
    )
    (net (code "118") (name "unconnected-(U20B-2A-Pad5)") (class "Default")
      (node (ref "U20") (pin "5") (pinfunction "2A_5") (pintype "input"))
    )
    (net (code "119") (name "unconnected-(U20C-3A-Pad9)") (class "Default")
      (node (ref "U20") (pin "9") (pinfunction "3A_9") (pintype "input"))
    )
    (net (code "120") (name "unconnected-(U21B-DNU-PadE1)") (class "Default")
      (node (ref "U21") (pin "E1") (pinfunction "DNU_E1") (pintype "passive"))
    )
    (net (code "121") (name "unconnected-(U21B-NC-PadA1)") (class "Default")
      (node (ref "U21") (pin "A1") (pinfunction "NC_A1") (pintype "passive"))
    )
    (net (code "122") (name "unconnected-(U21B-NC-PadA8)") (class "Default")
      (node (ref "U21") (pin "A8") (pinfunction "NC_A8") (pintype "passive"))
    )
    (net (code "123") (name "unconnected-(U21B-NC-PadC1)") (class "Default")
      (node (ref "U21") (pin "C1") (pinfunction "NC_C1") (pintype "passive"))
    )
    (net (code "124") (name "unconnected-(U21B-NC-PadD1)") (class "Default")
      (node (ref "U21") (pin "D1") (pinfunction "NC_D1") (pintype "passive"))
    )
    (net (code "125") (name "unconnected-(U21B-NC-PadH1)") (class "Default")
      (node (ref "U21") (pin "H1") (pinfunction "NC_H1") (pintype "passive"))
    )
    (net (code "126") (name "unconnected-(U21B-NC-PadH8)") (class "Default")
      (node (ref "U21") (pin "H8") (pinfunction "NC_H8") (pintype "passive"))
    )
    (net (code "127") (name "unconnected-(U21B-RFU-PadF7)") (class "Default")
      (node (ref "U21") (pin "F7") (pinfunction "RFU_F7") (pintype "passive"))
    )
    (net (code "128") (name "unconnected-(U21B-RFU-PadG1)") (class "Default")
      (node (ref "U21") (pin "G1") (pinfunction "RFU_G1") (pintype "passive"))
    )
    (net (code "129") (name "unconnected-(U22-Y-Pad4)") (class "Default")
      (node (ref "U22") (pin "4") (pinfunction "Y_4") (pintype "output"))
    )
    (net (code "130") (name "unconnected-(U23-RST-Pad3)") (class "Default")
      (node (ref "U23") (pin "3") (pinfunction "RST_3") (pintype "output"))
    )
  )
)
